# TSOC_GROVEY_WIFI_R0_9.net
KiCad netlist of a schematic drawn in EAGLE
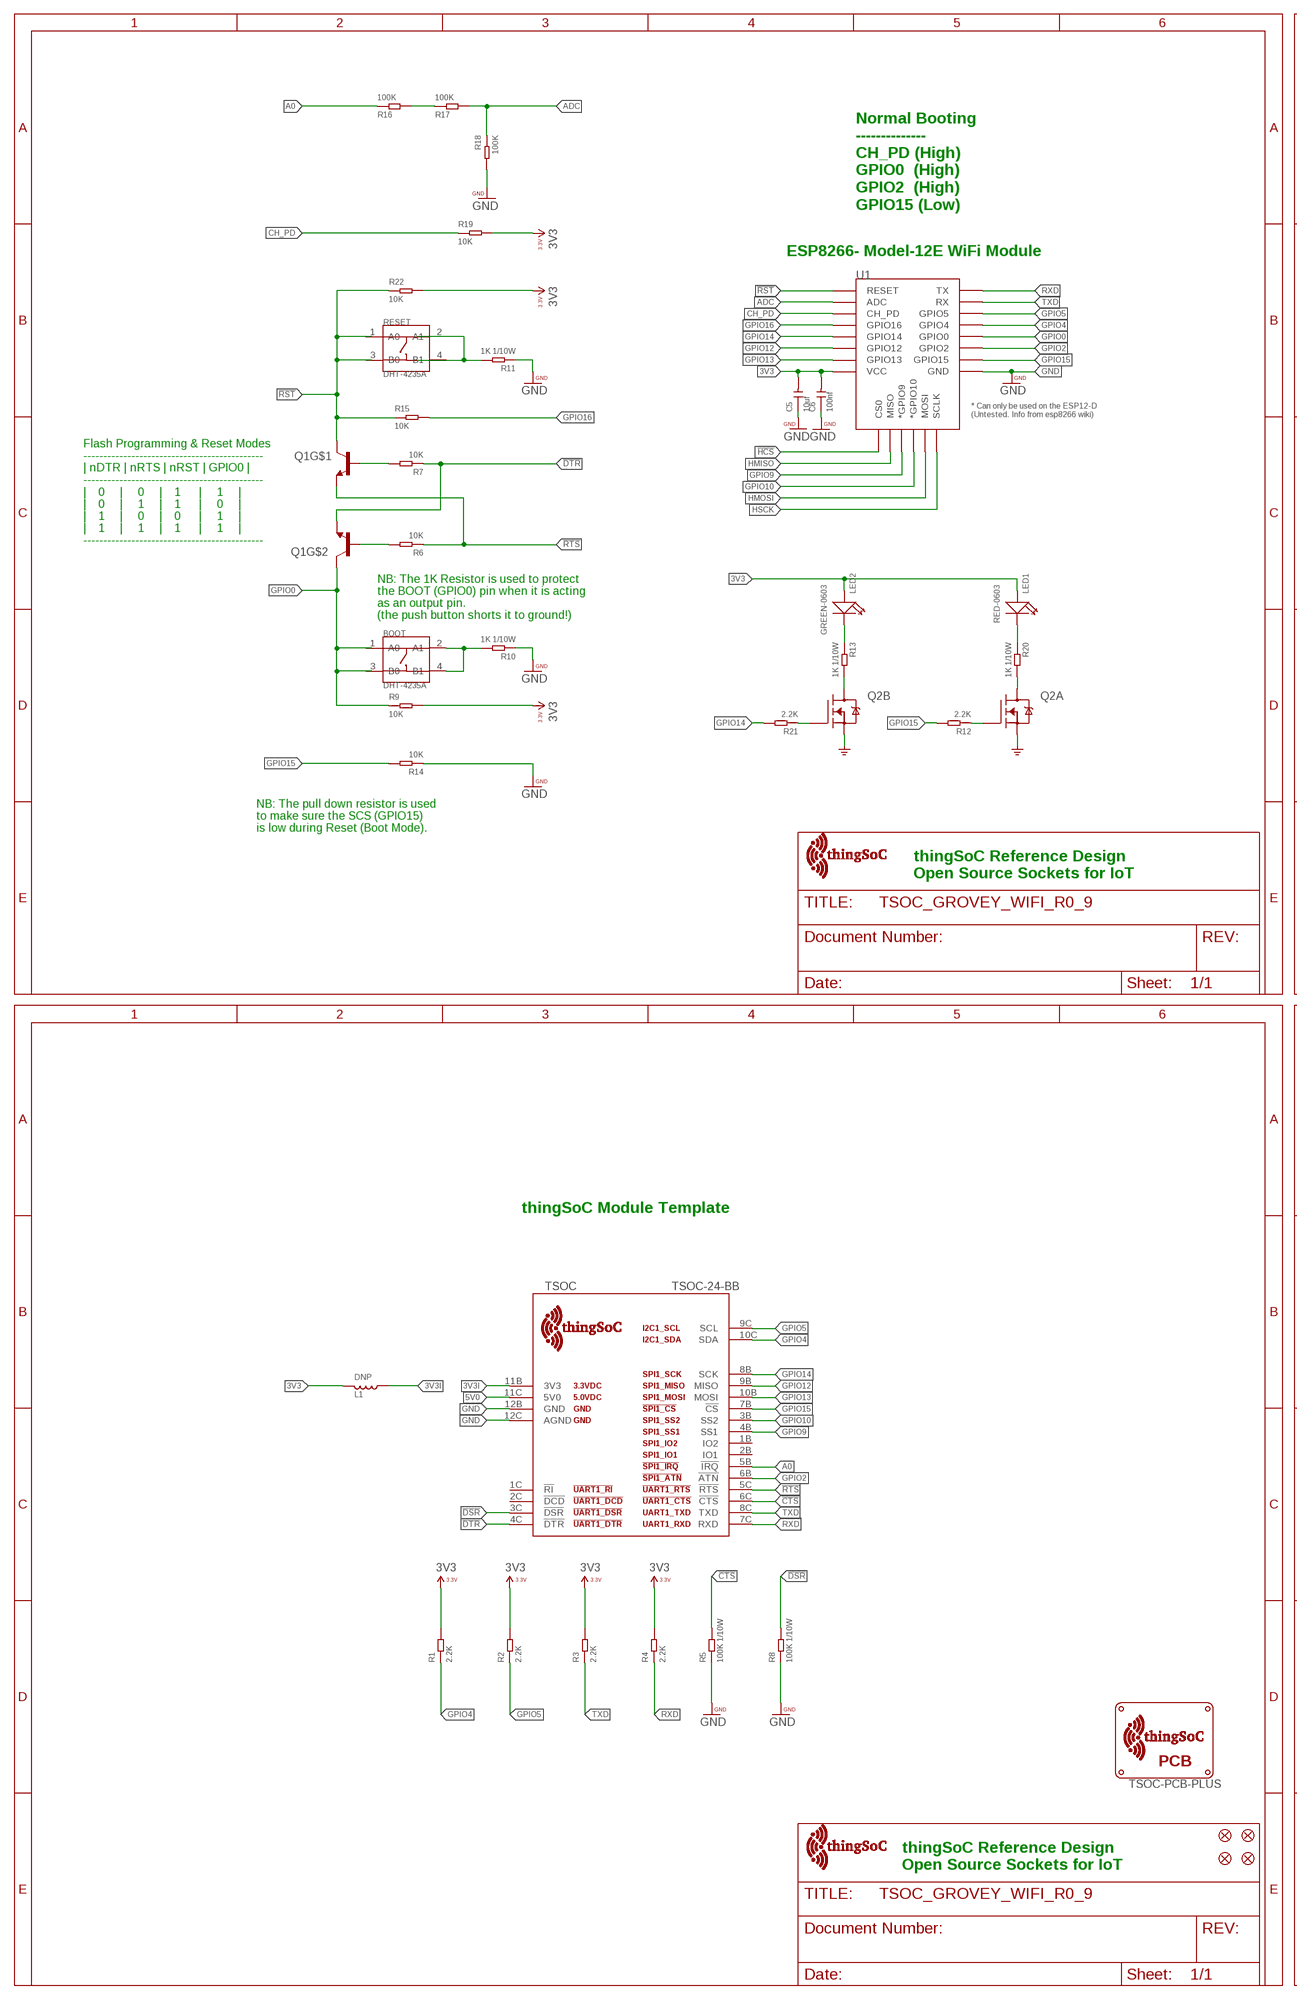
[diagram p0: schematic, sheet 1, part 1 of 2]
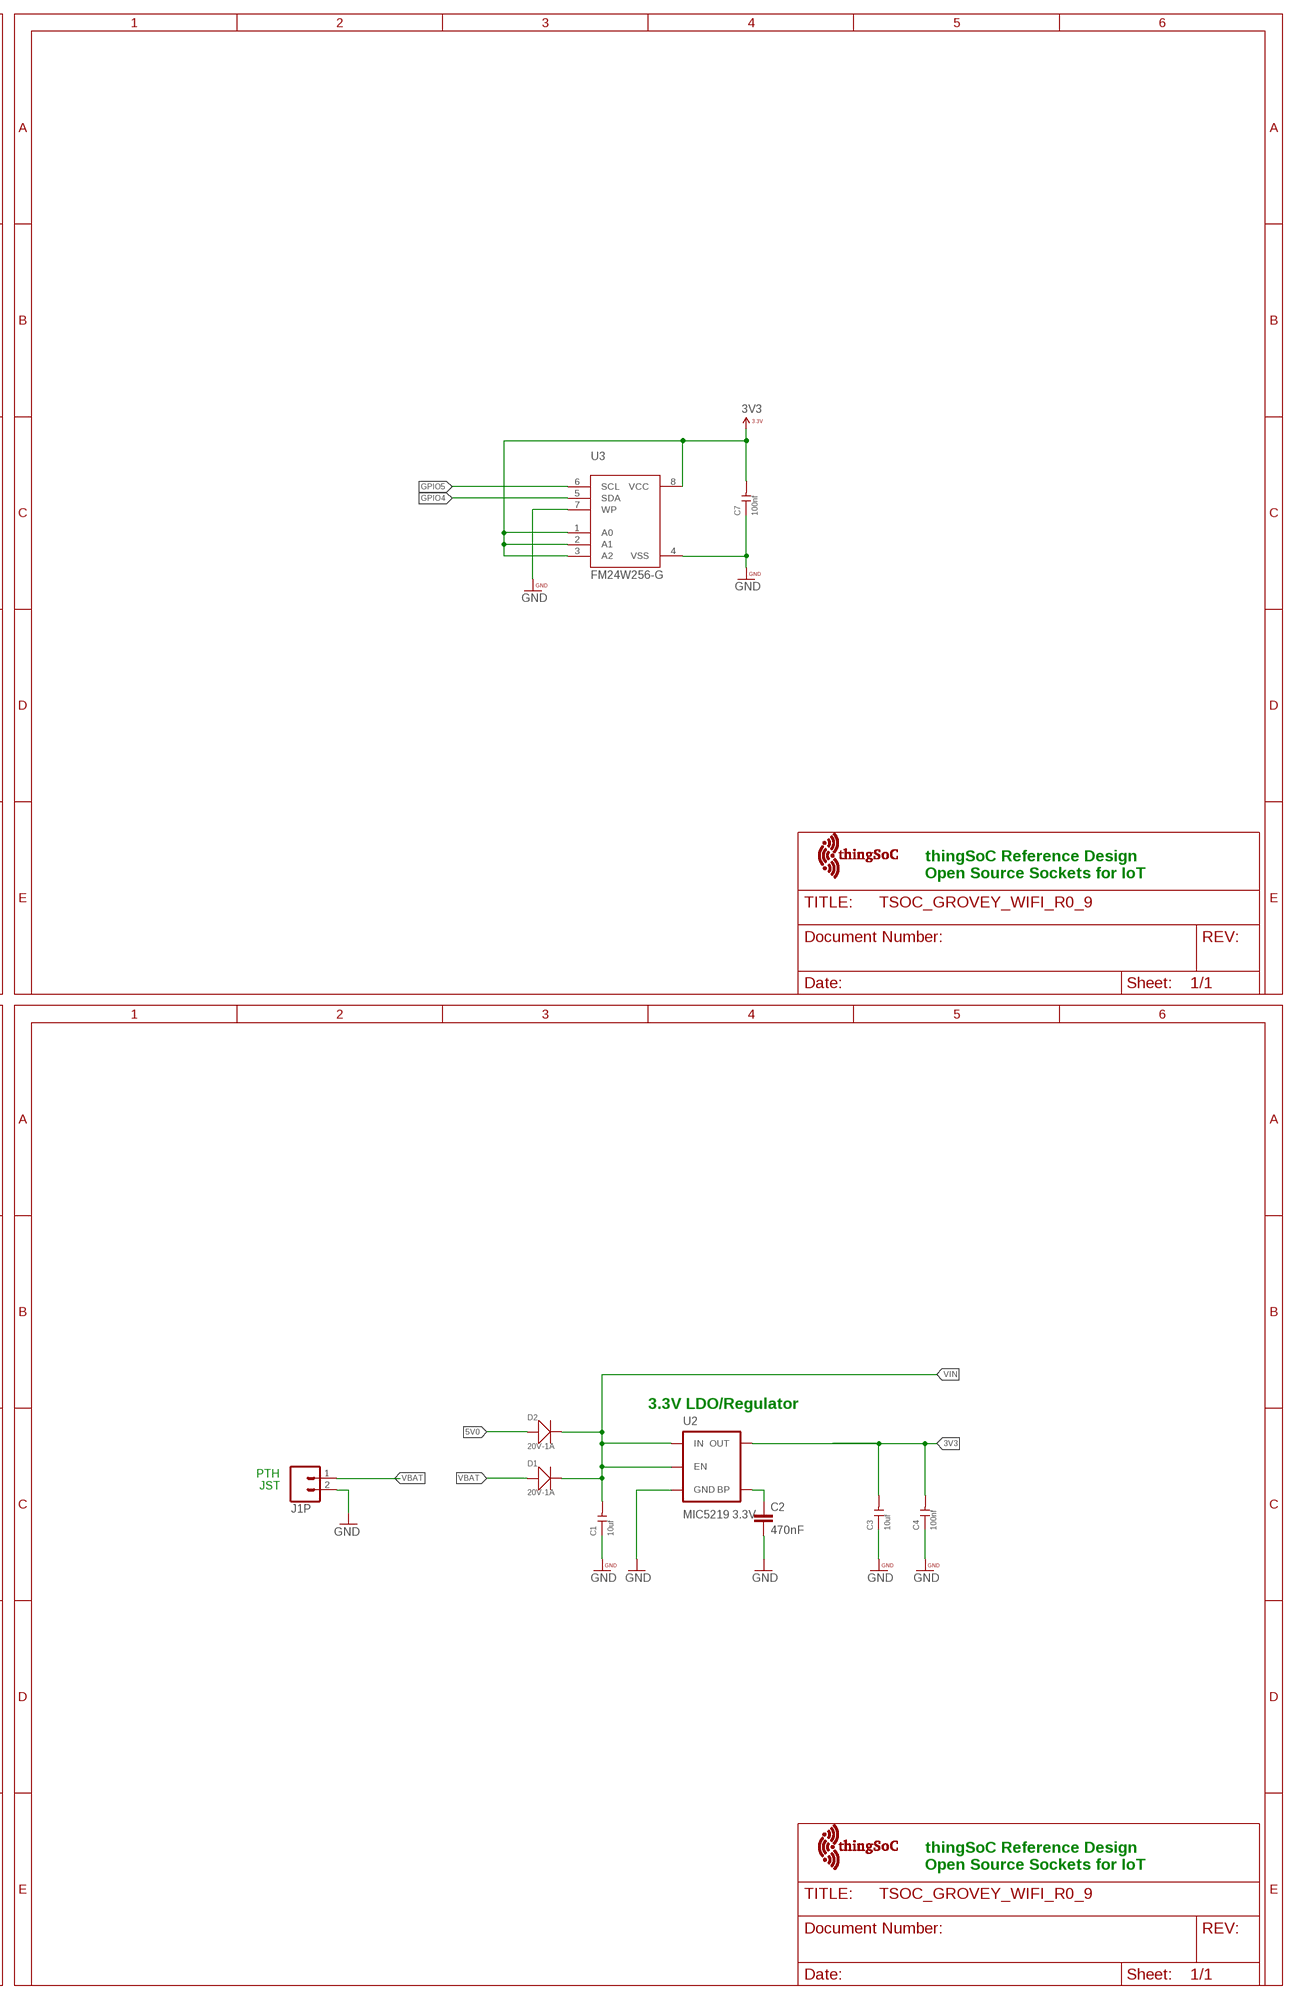
[diagram p1: schematic, sheet 1, part 2 of 2]

(export (version "E")
  (design (tool "Eeschema 10.0.6"))
  (components
    (comp (ref "BOOT")
      (value "DHT-4235A")
      (footprint "eagle-import:SW4-SMD-4.2X3.2X2.5MM")
      (libsource (lib "eagle-import") (part "SMD-BUTTON-TOP-DHT-4235A(4P-4.2X3.2MM)"))
    )
    (comp (ref "C1")
      (value "10uf")
      (footprint "eagle-import:C1206")
      (fields (field (name "MPN") "CC1206KKX5R8BB106"))
      (libsource (lib "eagle-import") (part "CERAMIC-10UF-25V-10%-X5R(1206)"))
    )
    (comp (ref "C2")
      (value "470nF")
      (footprint "eagle-import:0402-CAP")
      (libsource (lib "eagle-import") (part "CAP0402-CAP"))
    )
    (comp (ref "C3")
      (value "10uf")
      (footprint "eagle-import:C1206")
      (fields (field (name "MPN") "CC1206KKX5R8BB106"))
      (libsource (lib "eagle-import") (part "CERAMIC-10UF-25V-10%-X5R(1206)"))
    )
    (comp (ref "C4")
      (value "100nf")
      (footprint "eagle-import:C0603")
      (fields (field (name "MPN") "CC0603KRX7R9BB104"))
      (libsource (lib "eagle-import") (part "CERAMIC-100NF-50V-10%-X7R(0603)"))
    )
    (comp (ref "C5")
      (value "10uf")
      (footprint "eagle-import:C1206")
      (fields (field (name "MPN") "CC1206KKX5R8BB106"))
      (libsource (lib "eagle-import") (part "CERAMIC-10UF-25V-10%-X5R(1206)"))
    )
    (comp (ref "C6")
      (value "100nf")
      (footprint "eagle-import:C0603")
      (fields (field (name "MPN") "CC0603KRX7R9BB104"))
      (libsource (lib "eagle-import") (part "CERAMIC-100NF-50V-10%-X7R(0603)"))
    )
    (comp (ref "C7")
      (value "100nf")
      (footprint "eagle-import:C0603")
      (fields (field (name "MPN") "CC0603KRX7R9BB104"))
      (libsource (lib "eagle-import") (part "CERAMIC-100NF-50V-10%-X7R(0603)"))
    )
    (comp (ref "D1")
      (value "20V-1A")
      (footprint "eagle-import:SOD-123")
      (fields (field (name "MPN") "B5819W"))
      (libsource (lib "eagle-import") (part "SMD-DIODE-SCHOTTKY-20V-1A(SOD-123)"))
    )
    (comp (ref "D2")
      (value "20V-1A")
      (footprint "eagle-import:SOD-123")
      (fields (field (name "MPN") "B5819W"))
      (libsource (lib "eagle-import") (part "SMD-DIODE-SCHOTTKY-20V-1A(SOD-123)"))
    )
    (comp (ref "FID1")
      (value "FIDUCIALUFIDUCIAL")
      (footprint "eagle-import:MICRO-FIDUCIAL")
      (libsource (lib "eagle-import") (part "FIDUCIALUFIDUCIAL"))
    )
    (comp (ref "FID2")
      (value "FIDUCIALUFIDUCIAL")
      (footprint "eagle-import:MICRO-FIDUCIAL")
      (libsource (lib "eagle-import") (part "FIDUCIALUFIDUCIAL"))
    )
    (comp (ref "FID3")
      (value "FIDUCIALUFIDUCIAL")
      (footprint "eagle-import:MICRO-FIDUCIAL")
      (libsource (lib "eagle-import") (part "FIDUCIALUFIDUCIAL"))
    )
    (comp (ref "FID4")
      (value "FIDUCIALUFIDUCIAL")
      (footprint "eagle-import:MICRO-FIDUCIAL")
      (libsource (lib "eagle-import") (part "FIDUCIALUFIDUCIAL"))
    )
    (comp (ref "J1P")
      (value "M02-JST-2-PTH-NO_SILK")
      (footprint "eagle-import:JST-2-PTH-NS")
      (libsource (lib "eagle-import") (part "M02-JST-2-PTH-NO_SILK"))
    )
    (comp (ref "L1")
      (value "DNP")
      (footprint "eagle-import:L0603")
      (fields (field (name "MPN") "BLM18AG121SN1D"))
      (libsource (lib "eagle-import") (part "SMD-FERRITE-CHIP-120-OHM-500MA(0603)"))
    )
    (comp (ref "LED1")
      (value "RED-0603")
      (footprint "eagle-import:LED-0603")
      (fields (field (name "MPN") "19-217-R6C-AL1M2VY-3T"))
      (libsource (lib "eagle-import") (part "LED-SMD-RED-DIFFUSED(0603)"))
    )
    (comp (ref "LED2")
      (value "GREEN-0603")
      (footprint "eagle-import:LED-0603")
      (fields (field (name "MPN") "19-217-G7C-AN1P2-3T"))
      (libsource (lib "eagle-import") (part "SMD-LED-CLEAR-GREEN(0603)"))
    )
    (comp (ref "PCB")
      (value "TSOC-PCB-PLUS")
      (footprint "eagle-import:TSOC-BB-BRD-PLUS-DIM")
      (libsource (lib "eagle-import") (part "TSOC-PCB-PLUS"))
    )
    (comp (ref "Q1")
      (value "MMBT2222A")
      (footprint "eagle-import:SOT363")
      (libsource (lib "eagle-import") (part "MMDT3904"))
    )
    (comp (ref "Q2")
      (value "FDG1024NZ")
      (footprint "eagle-import:SOT95P280X110-6N")
      (libsource (lib "eagle-import") (part "FDG1024NZ"))
    )
    (comp (ref "R1")
      (value "2.2K")
      (footprint "eagle-import:R0603")
      (fields (field (name "MPN") "RC0603JR-072K2L"))
      (libsource (lib "eagle-import") (part "SMD-RES-2.2K-5%-1/10W(0603)"))
    )
    (comp (ref "R2")
      (value "2.2K")
      (footprint "eagle-import:R0603")
      (fields (field (name "MPN") "RC0603JR-072K2L"))
      (libsource (lib "eagle-import") (part "SMD-RES-2.2K-5%-1/10W(0603)"))
    )
    (comp (ref "R3")
      (value "2.2K")
      (footprint "eagle-import:R0603")
      (fields (field (name "MPN") "RC0603JR-072K2L"))
      (libsource (lib "eagle-import") (part "SMD-RES-2.2K-5%-1/10W(0603)"))
    )
    (comp (ref "R4")
      (value "2.2K")
      (footprint "eagle-import:R0603")
      (fields (field (name "MPN") "RC0603JR-072K2L"))
      (libsource (lib "eagle-import") (part "SMD-RES-2.2K-5%-1/10W(0603)"))
    )
    (comp (ref "R5")
      (value "100K 1/10W")
      (footprint "eagle-import:R0603")
      (fields (field (name "MPN") "RC0603JR-07100KL"))
      (libsource (lib "eagle-import") (part "SMD-RES-100K-5%-1/10W(0603)"))
    )
    (comp (ref "R6")
      (value "10K")
      (footprint "eagle-import:R0603")
      (fields (field (name "MPN") "RC0603FR-0710KL"))
      (libsource (lib "eagle-import") (part "SMD-RES-10K-1%-1/10W(0603)"))
    )
    (comp (ref "R7")
      (value "10K")
      (footprint "eagle-import:R0603")
      (fields (field (name "MPN") "RC0603FR-0710KL"))
      (libsource (lib "eagle-import") (part "SMD-RES-10K-1%-1/10W(0603)"))
    )
    (comp (ref "R8")
      (value "100K 1/10W")
      (footprint "eagle-import:R0603")
      (fields (field (name "MPN") "RC0603JR-07100KL"))
      (libsource (lib "eagle-import") (part "SMD-RES-100K-5%-1/10W(0603)"))
    )
    (comp (ref "R9")
      (value "10K")
      (footprint "eagle-import:R0603")
      (fields (field (name "MPN") "RC0603FR-0710KL"))
      (libsource (lib "eagle-import") (part "SMD-RES-10K-1%-1/10W(0603)"))
    )
    (comp (ref "R10")
      (value "1K 1/10W")
      (footprint "eagle-import:R0603")
      (fields (field (name "MPN") "RC0603JR-071KL"))
      (libsource (lib "eagle-import") (part "SMD-RES-1K-5%-1/10W(0603)"))
    )
    (comp (ref "R11")
      (value "1K 1/10W")
      (footprint "eagle-import:R0603")
      (fields (field (name "MPN") "RC0603JR-071KL"))
      (libsource (lib "eagle-import") (part "SMD-RES-1K-5%-1/10W(0603)"))
    )
    (comp (ref "R12")
      (value "2.2K")
      (footprint "eagle-import:R0603")
      (fields (field (name "MPN") "RC0603JR-072K2L"))
      (libsource (lib "eagle-import") (part "SMD-RES-2.2K-5%-1/10W(0603)"))
    )
    (comp (ref "R13")
      (value "1K 1/10W")
      (footprint "eagle-import:R0603")
      (fields (field (name "MPN") "RC0603JR-071KL"))
      (libsource (lib "eagle-import") (part "SMD-RES-1K-5%-1/10W(0603)"))
    )
    (comp (ref "R14")
      (value "10K")
      (footprint "eagle-import:R0603")
      (fields (field (name "MPN") "RC0603FR-0710KL"))
      (libsource (lib "eagle-import") (part "SMD-RES-10K-1%-1/10W(0603)"))
    )
    (comp (ref "R15")
      (value "10K")
      (footprint "eagle-import:R0603")
      (fields (field (name "MPN") "RC0603FR-0710KL"))
      (libsource (lib "eagle-import") (part "SMD-RES-10K-1%-1/10W(0603)"))
    )
    (comp (ref "R16")
      (value "100K")
      (footprint "eagle-import:R0603")
      (fields (field (name "MPN") "RC0603FR-07100KL"))
      (libsource (lib "eagle-import") (part "SMD-RES-100K-1%-1/10W(0603)"))
    )
    (comp (ref "R17")
      (value "100K")
      (footprint "eagle-import:R0603")
      (fields (field (name "MPN") "RC0603FR-07100KL"))
      (libsource (lib "eagle-import") (part "SMD-RES-100K-1%-1/10W(0603)"))
    )
    (comp (ref "R18")
      (value "100K")
      (footprint "eagle-import:R0603")
      (fields (field (name "MPN") "RC0603FR-07100KL"))
      (libsource (lib "eagle-import") (part "SMD-RES-100K-1%-1/10W(0603)"))
    )
    (comp (ref "R19")
      (value "10K")
      (footprint "eagle-import:R0603")
      (fields (field (name "MPN") "RC0603FR-0710KL"))
      (libsource (lib "eagle-import") (part "SMD-RES-10K-1%-1/10W(0603)"))
    )
    (comp (ref "R20")
      (value "1K 1/10W")
      (footprint "eagle-import:R0603")
      (fields (field (name "MPN") "RC0603JR-071KL"))
      (libsource (lib "eagle-import") (part "SMD-RES-1K-5%-1/10W(0603)"))
    )
    (comp (ref "R21")
      (value "2.2K")
      (footprint "eagle-import:R0603")
      (fields (field (name "MPN") "RC0603JR-072K2L"))
      (libsource (lib "eagle-import") (part "SMD-RES-2.2K-5%-1/10W(0603)"))
    )
    (comp (ref "R22")
      (value "10K")
      (footprint "eagle-import:R0603")
      (fields (field (name "MPN") "RC0603FR-0710KL"))
      (libsource (lib "eagle-import") (part "SMD-RES-10K-1%-1/10W(0603)"))
    )
    (comp (ref "RESET")
      (value "DHT-4235A")
      (footprint "eagle-import:SW4-SMD-4.2X3.2X2.5MM")
      (libsource (lib "eagle-import") (part "SMD-BUTTON-TOP-DHT-4235A(4P-4.2X3.2MM)"))
    )
    (comp (ref "TSOC")
      (value "TSOC-24-BB")
      (footprint "eagle-import:TSOC-BB-S24")
      (libsource (lib "eagle-import") (part "TSOC-24-BB"))
    )
    (comp (ref "U$22")
      (value "TSOC-LOGO-MED")
      (footprint "eagle-import:TSOC-LOGO-MED")
      (libsource (lib "eagle-import") (part "TSOC-LOGO-MED"))
    )
    (comp (ref "U$23")
      (value "TSOC-LOGO-MED")
      (footprint "eagle-import:TSOC-LOGO-MED")
      (libsource (lib "eagle-import") (part "TSOC-LOGO-MED"))
    )
    (comp (ref "U$26")
      (value "TSOC-LOGO-MED")
      (footprint "eagle-import:TSOC-LOGO-MED")
      (libsource (lib "eagle-import") (part "TSOC-LOGO-MED"))
    )
    (comp (ref "U$28")
      (value "TSOC-LOGO-MED")
      (footprint "eagle-import:TSOC-LOGO-MED")
      (libsource (lib "eagle-import") (part "TSOC-LOGO-MED"))
    )
    (comp (ref "U1")
      (value "ESP12ESMD")
      (footprint "eagle-import:ESP12E-SMD")
      (libsource (lib "eagle-import") (part "ESP12ESMD"))
    )
    (comp (ref "U2")
      (value "MIC5219 3.3V")
      (footprint "eagle-import:SOT23-5")
      (libsource (lib "eagle-import") (part "V_REG_MIC52193.3V"))
    )
    (comp (ref "U3")
      (value "FM24W256-G")
      (footprint "eagle-import:SO08")
      (libsource (lib "eagle-import") (part "FM24W256-G"))
    )
  )
  (nets
    (net (code "1") (name "/~{CTS}") (class "Default")
      (node (ref "R5") (pin "2") (pinfunction "2_2") (pintype "passive"))
      (node (ref "TSOC") (pin "6C") (pinfunction "~{CTS}_6C") (pintype "bidirectional"))
    )
    (net (code "2") (name "/~{DSR}") (class "Default")
      (node (ref "R8") (pin "2") (pinfunction "2_2") (pintype "passive"))
      (node (ref "TSOC") (pin "3C") (pinfunction "~{DSR}_3C") (pintype "bidirectional"))
    )
    (net (code "3") (name "/~{DTR}") (class "Default")
      (node (ref "Q1") (pin "1") (pinfunction "E_1") (pintype "passive"))
      (node (ref "R7") (pin "1") (pinfunction "1_1") (pintype "passive"))
      (node (ref "TSOC") (pin "4C") (pinfunction "~{DTR}_4C") (pintype "bidirectional"))
    )
    (net (code "4") (name "/~{HCS}") (class "Default")
      (node (ref "U1") (pin "CS0") (pinfunction "CS0_CS0") (pintype "bidirectional"))
    )
    (net (code "5") (name "/~{RST}") (class "Default")
      (node (ref "Q1") (pin "3") (pinfunction "C_3") (pintype "passive"))
      (node (ref "R15") (pin "1") (pinfunction "1_1") (pintype "passive"))
      (node (ref "R22") (pin "1") (pinfunction "1_1") (pintype "passive"))
      (node (ref "RESET") (pin "1") (pinfunction "A0_1") (pintype "bidirectional"))
      (node (ref "RESET") (pin "3") (pinfunction "B0_3") (pintype "bidirectional"))
      (node (ref "U1") (pin "RESET") (pinfunction "RESET_RESET") (pintype "bidirectional"))
    )
    (net (code "6") (name "/~{RTS}") (class "Default")
      (node (ref "Q1") (pin "4") (pinfunction "E_4") (pintype "passive"))
      (node (ref "R6") (pin "1") (pinfunction "1_1") (pintype "passive"))
      (node (ref "TSOC") (pin "5C") (pinfunction "~{RTS}_5C") (pintype "bidirectional"))
    )
    (net (code "7") (name "3V3") (class "Default")
      (node (ref "C3") (pin "2") (pinfunction "2_2") (pintype "passive"))
      (node (ref "C4") (pin "2") (pinfunction "2_2") (pintype "passive"))
      (node (ref "C5") (pin "2") (pinfunction "2_2") (pintype "passive"))
      (node (ref "C6") (pin "2") (pinfunction "2_2") (pintype "passive"))
      (node (ref "C7") (pin "2") (pinfunction "2_2") (pintype "passive"))
      (node (ref "L1") (pin "1") (pinfunction "1_1") (pintype "passive"))
      (node (ref "LED1") (pin "+") (pinfunction "+_+") (pintype "passive"))
      (node (ref "LED2") (pin "+") (pinfunction "+_+") (pintype "passive"))
      (node (ref "R1") (pin "2") (pinfunction "2_2") (pintype "passive"))
      (node (ref "R19") (pin "2") (pinfunction "2_2") (pintype "passive"))
      (node (ref "R2") (pin "2") (pinfunction "2_2") (pintype "passive"))
      (node (ref "R22") (pin "2") (pinfunction "2_2") (pintype "passive"))
      (node (ref "R3") (pin "2") (pinfunction "2_2") (pintype "passive"))
      (node (ref "R4") (pin "2") (pinfunction "2_2") (pintype "passive"))
      (node (ref "R9") (pin "2") (pinfunction "2_2") (pintype "passive"))
      (node (ref "U1") (pin "VCC") (pinfunction "VCC_VCC") (pintype "bidirectional"))
      (node (ref "U2") (pin "5") (pinfunction "OUT_5") (pintype "passive"))
      (node (ref "U3") (pin "1") (pinfunction "A0_1") (pintype "bidirectional"))
      (node (ref "U3") (pin "2") (pinfunction "A1_2") (pintype "bidirectional"))
      (node (ref "U3") (pin "3") (pinfunction "A2_3") (pintype "bidirectional"))
      (node (ref "U3") (pin "8") (pinfunction "VCC_8") (pintype "power_in"))
    )
    (net (code "8") (name "3V3I") (class "Default")
      (node (ref "L1") (pin "2") (pinfunction "2_2") (pintype "passive"))
      (node (ref "TSOC") (pin "11B") (pinfunction "3V3_11B") (pintype "bidirectional"))
    )
    (net (code "9") (name "5V0") (class "Default")
      (node (ref "D2") (pin "+") (pinfunction "+_+") (pintype "passive"))
      (node (ref "TSOC") (pin "11C") (pinfunction "5V0_11C") (pintype "bidirectional"))
    )
    (net (code "10") (name "A0") (class "Default")
      (node (ref "R16") (pin "1") (pinfunction "1_1") (pintype "passive"))
      (node (ref "TSOC") (pin "5B") (pinfunction "~{IRQ}_5B") (pintype "bidirectional"))
    )
    (net (code "11") (name "ADC") (class "Default")
      (node (ref "R17") (pin "2") (pinfunction "2_2") (pintype "passive"))
      (node (ref "R18") (pin "1") (pinfunction "1_1") (pintype "passive"))
      (node (ref "U1") (pin "ADC") (pinfunction "ADC_ADC") (pintype "bidirectional"))
    )
    (net (code "12") (name "CH_PD") (class "Default")
      (node (ref "R19") (pin "1") (pinfunction "1_1") (pintype "passive"))
      (node (ref "U1") (pin "CH_PD") (pinfunction "CH_PD_CH_PD") (pintype "bidirectional"))
    )
    (net (code "13") (name "GND") (class "Default")
      (node (ref "C1") (pin "1") (pinfunction "1_1") (pintype "passive"))
      (node (ref "C2") (pin "2") (pinfunction "2_2") (pintype "passive"))
      (node (ref "C3") (pin "1") (pinfunction "1_1") (pintype "passive"))
      (node (ref "C4") (pin "1") (pinfunction "1_1") (pintype "passive"))
      (node (ref "C5") (pin "1") (pinfunction "1_1") (pintype "passive"))
      (node (ref "C6") (pin "1") (pinfunction "1_1") (pintype "passive"))
      (node (ref "C7") (pin "1") (pinfunction "1_1") (pintype "passive"))
      (node (ref "J1P") (pin "2") (pinfunction "2_2") (pintype "passive"))
      (node (ref "Q2") (pin "1") (pinfunction "S_1") (pintype "passive"))
      (node (ref "Q2") (pin "4") (pinfunction "S_4") (pintype "passive"))
      (node (ref "R10") (pin "1") (pinfunction "1_1") (pintype "passive"))
      (node (ref "R11") (pin "1") (pinfunction "1_1") (pintype "passive"))
      (node (ref "R14") (pin "1") (pinfunction "1_1") (pintype "passive"))
      (node (ref "R18") (pin "2") (pinfunction "2_2") (pintype "passive"))
      (node (ref "R5") (pin "1") (pinfunction "1_1") (pintype "passive"))
      (node (ref "R8") (pin "1") (pinfunction "1_1") (pintype "passive"))
      (node (ref "TSOC") (pin "12B") (pinfunction "GND_12B") (pintype "bidirectional"))
      (node (ref "TSOC") (pin "12C") (pinfunction "AGND_12C") (pintype "bidirectional"))
      (node (ref "U1") (pin "GND") (pinfunction "GND_GND") (pintype "bidirectional"))
      (node (ref "U2") (pin "2") (pinfunction "GND_2") (pintype "input"))
      (node (ref "U3") (pin "4") (pinfunction "VSS_4") (pintype "power_in"))
      (node (ref "U3") (pin "7") (pinfunction "WP_7") (pintype "bidirectional"))
    )
    (net (code "14") (name "GPIO0") (class "Default")
      (node (ref "BOOT") (pin "1") (pinfunction "A0_1") (pintype "bidirectional"))
      (node (ref "BOOT") (pin "3") (pinfunction "B0_3") (pintype "bidirectional"))
      (node (ref "Q1") (pin "6") (pinfunction "C_6") (pintype "passive"))
      (node (ref "R9") (pin "1") (pinfunction "1_1") (pintype "passive"))
      (node (ref "U1") (pin "GPIO0") (pinfunction "GPIO0_GPIO0") (pintype "bidirectional"))
    )
    (net (code "15") (name "GPIO2") (class "Default")
      (node (ref "TSOC") (pin "6B") (pinfunction "~{ATN}_6B") (pintype "bidirectional"))
      (node (ref "U1") (pin "GPIO2") (pinfunction "GPIO2_GPIO2") (pintype "bidirectional"))
    )
    (net (code "16") (name "GPIO4") (class "Default")
      (node (ref "R1") (pin "1") (pinfunction "1_1") (pintype "passive"))
      (node (ref "TSOC") (pin "10C") (pinfunction "SDA_10C") (pintype "bidirectional"))
      (node (ref "U1") (pin "GPIO4") (pinfunction "GPIO4_GPIO4") (pintype "bidirectional"))
      (node (ref "U3") (pin "5") (pinfunction "SDA_5") (pintype "bidirectional"))
    )
    (net (code "17") (name "GPIO5") (class "Default")
      (node (ref "R2") (pin "1") (pinfunction "1_1") (pintype "passive"))
      (node (ref "TSOC") (pin "9C") (pinfunction "SCL_9C") (pintype "bidirectional"))
      (node (ref "U1") (pin "GPIO5") (pinfunction "GPIO5_GPIO5") (pintype "bidirectional"))
      (node (ref "U3") (pin "6") (pinfunction "SCL_6") (pintype "bidirectional"))
    )
    (net (code "18") (name "GPIO9") (class "Default")
      (node (ref "TSOC") (pin "4B") (pinfunction "SS1_4B") (pintype "bidirectional"))
      (node (ref "U1") (pin "GPIO9") (pinfunction "*GPIO9_GPIO9") (pintype "bidirectional"))
    )
    (net (code "19") (name "GPIO10") (class "Default")
      (node (ref "TSOC") (pin "3B") (pinfunction "SS2_3B") (pintype "bidirectional"))
      (node (ref "U1") (pin "GPIO10") (pinfunction "*GPIO10_GPIO10") (pintype "bidirectional"))
    )
    (net (code "20") (name "GPIO12") (class "Default")
      (node (ref "TSOC") (pin "9B") (pinfunction "MISO_9B") (pintype "bidirectional"))
      (node (ref "U1") (pin "GPIO12") (pinfunction "GPIO12_GPIO12") (pintype "bidirectional"))
    )
    (net (code "21") (name "GPIO13") (class "Default")
      (node (ref "TSOC") (pin "10B") (pinfunction "MOSI_10B") (pintype "bidirectional"))
      (node (ref "U1") (pin "GPIO13") (pinfunction "GPIO13_GPIO13") (pintype "bidirectional"))
    )
    (net (code "22") (name "GPIO14") (class "Default")
      (node (ref "R21") (pin "2") (pinfunction "2_2") (pintype "passive"))
      (node (ref "TSOC") (pin "8B") (pinfunction "SCK_8B") (pintype "bidirectional"))
      (node (ref "U1") (pin "GPIO14") (pinfunction "GPIO14_GPIO14") (pintype "bidirectional"))
    )
    (net (code "23") (name "GPIO15") (class "Default")
      (node (ref "R12") (pin "2") (pinfunction "2_2") (pintype "passive"))
      (node (ref "R14") (pin "2") (pinfunction "2_2") (pintype "passive"))
      (node (ref "TSOC") (pin "7B") (pinfunction "~{CS}_7B") (pintype "bidirectional"))
      (node (ref "U1") (pin "GPIO15") (pinfunction "GPIO15_GPIO15") (pintype "bidirectional"))
    )
    (net (code "24") (name "GPIO16") (class "Default")
      (node (ref "R15") (pin "2") (pinfunction "2_2") (pintype "passive"))
      (node (ref "U1") (pin "GPIO16") (pinfunction "GPIO16_GPIO16") (pintype "bidirectional"))
    )
    (net (code "25") (name "HMISO") (class "Default")
      (node (ref "U1") (pin "MISO") (pinfunction "MISO_MISO") (pintype "bidirectional"))
    )
    (net (code "26") (name "HMOSI") (class "Default")
      (node (ref "U1") (pin "MOSI") (pinfunction "MOSI_MOSI") (pintype "bidirectional"))
    )
    (net (code "27") (name "HSCK") (class "Default")
      (node (ref "U1") (pin "SCLK") (pinfunction "SCLK_SCLK") (pintype "bidirectional"))
    )
    (net (code "28") (name "Net-(BOOT-A1)") (class "Default")
      (node (ref "BOOT") (pin "2") (pinfunction "A1_2") (pintype "bidirectional"))
      (node (ref "BOOT") (pin "4") (pinfunction "B1_4") (pintype "bidirectional"))
      (node (ref "R10") (pin "2") (pinfunction "2_2") (pintype "passive"))
    )
    (net (code "29") (name "Net-(LED1-Pad-)") (class "Default")
      (node (ref "LED1") (pin "-") (pinfunction "-_-") (pintype "passive"))
      (node (ref "R20") (pin "1") (pinfunction "1_1") (pintype "passive"))
    )
    (net (code "30") (name "Net-(LED2-Pad-)") (class "Default")
      (node (ref "LED2") (pin "-") (pinfunction "-_-") (pintype "passive"))
      (node (ref "R13") (pin "1") (pinfunction "1_1") (pintype "passive"))
    )
    (net (code "31") (name "Net-(Q1A-B)") (class "Default")
      (node (ref "Q1") (pin "5") (pinfunction "B_5") (pintype "passive"))
      (node (ref "R7") (pin "2") (pinfunction "2_2") (pintype "passive"))
    )
    (net (code "32") (name "Net-(Q1B-B)") (class "Default")
      (node (ref "Q1") (pin "2") (pinfunction "B_2") (pintype "passive"))
      (node (ref "R6") (pin "2") (pinfunction "2_2") (pintype "passive"))
    )
    (net (code "33") (name "Net-(Q2A-D)") (class "Default")
      (node (ref "Q2") (pin "6") (pinfunction "D_6") (pintype "passive"))
      (node (ref "R20") (pin "2") (pinfunction "2_2") (pintype "passive"))
    )
    (net (code "34") (name "Net-(Q2A-G)") (class "Default")
      (node (ref "Q2") (pin "2") (pinfunction "G_2") (pintype "passive"))
      (node (ref "R12") (pin "1") (pinfunction "1_1") (pintype "passive"))
    )
    (net (code "35") (name "Net-(Q2B-D)") (class "Default")
      (node (ref "Q2") (pin "3") (pinfunction "D_3") (pintype "passive"))
      (node (ref "R13") (pin "2") (pinfunction "2_2") (pintype "passive"))
    )
    (net (code "36") (name "Net-(Q2B-G)") (class "Default")
      (node (ref "Q2") (pin "5") (pinfunction "G_5") (pintype "passive"))
      (node (ref "R21") (pin "1") (pinfunction "1_1") (pintype "passive"))
    )
    (net (code "37") (name "Net-(R16-Pad2)") (class "Default")
      (node (ref "R16") (pin "2") (pinfunction "2_2") (pintype "passive"))
      (node (ref "R17") (pin "1") (pinfunction "1_1") (pintype "passive"))
    )
    (net (code "38") (name "Net-(RESET-A1)") (class "Default")
      (node (ref "R11") (pin "2") (pinfunction "2_2") (pintype "passive"))
      (node (ref "RESET") (pin "2") (pinfunction "A1_2") (pintype "bidirectional"))
      (node (ref "RESET") (pin "4") (pinfunction "B1_4") (pintype "bidirectional"))
    )
    (net (code "39") (name "Net-(U2-BP)") (class "Default")
      (node (ref "C2") (pin "1") (pinfunction "1_1") (pintype "passive"))
      (node (ref "U2") (pin "4") (pinfunction "BP_4") (pintype "input"))
    )
    (net (code "40") (name "RXD") (class "Default")
      (node (ref "R4") (pin "1") (pinfunction "1_1") (pintype "passive"))
      (node (ref "TSOC") (pin "7C") (pinfunction "RXD_7C") (pintype "bidirectional"))
      (node (ref "U1") (pin "TXD0") (pinfunction "TX_TXD0") (pintype "bidirectional"))
    )
    (net (code "41") (name "TXD") (class "Default")
      (node (ref "R3") (pin "1") (pinfunction "1_1") (pintype "passive"))
      (node (ref "TSOC") (pin "8C") (pinfunction "TXD_8C") (pintype "bidirectional"))
      (node (ref "U1") (pin "RXD0") (pinfunction "RX_RXD0") (pintype "bidirectional"))
    )
    (net (code "42") (name "VBAT") (class "Default")
      (node (ref "D1") (pin "+") (pinfunction "+_+") (pintype "passive"))
      (node (ref "J1P") (pin "1") (pinfunction "1_1") (pintype "passive"))
    )
    (net (code "43") (name "VIN") (class "Default")
      (node (ref "C1") (pin "2") (pinfunction "2_2") (pintype "passive"))
      (node (ref "D1") (pin "-") (pinfunction "-_-") (pintype "passive"))
      (node (ref "D2") (pin "-") (pinfunction "-_-") (pintype "passive"))
      (node (ref "U2") (pin "1") (pinfunction "IN_1") (pintype "input"))
      (node (ref "U2") (pin "3") (pinfunction "EN_3") (pintype "input"))
    )
    (net (code "44") (name "unconnected-(TSOC-IO1-Pad2B)") (class "Default")
      (node (ref "TSOC") (pin "2B") (pinfunction "IO1_2B") (pintype "bidirectional"))
    )
    (net (code "45") (name "unconnected-(TSOC-IO2-Pad1B)") (class "Default")
      (node (ref "TSOC") (pin "1B") (pinfunction "IO2_1B") (pintype "bidirectional"))
    )
    (net (code "46") (name "unconnected-(TSOC-~{DCD}-Pad2C)") (class "Default")
      (node (ref "TSOC") (pin "2C") (pinfunction "~{DCD}_2C") (pintype "bidirectional"))
    )
    (net (code "47") (name "unconnected-(TSOC-~{RI}-Pad1C)") (class "Default")
      (node (ref "TSOC") (pin "1C") (pinfunction "~{RI}_1C") (pintype "bidirectional"))
    )
  )
)
